# SFFV_10.net
KiCad netlist of a schematic drawn in EAGLE
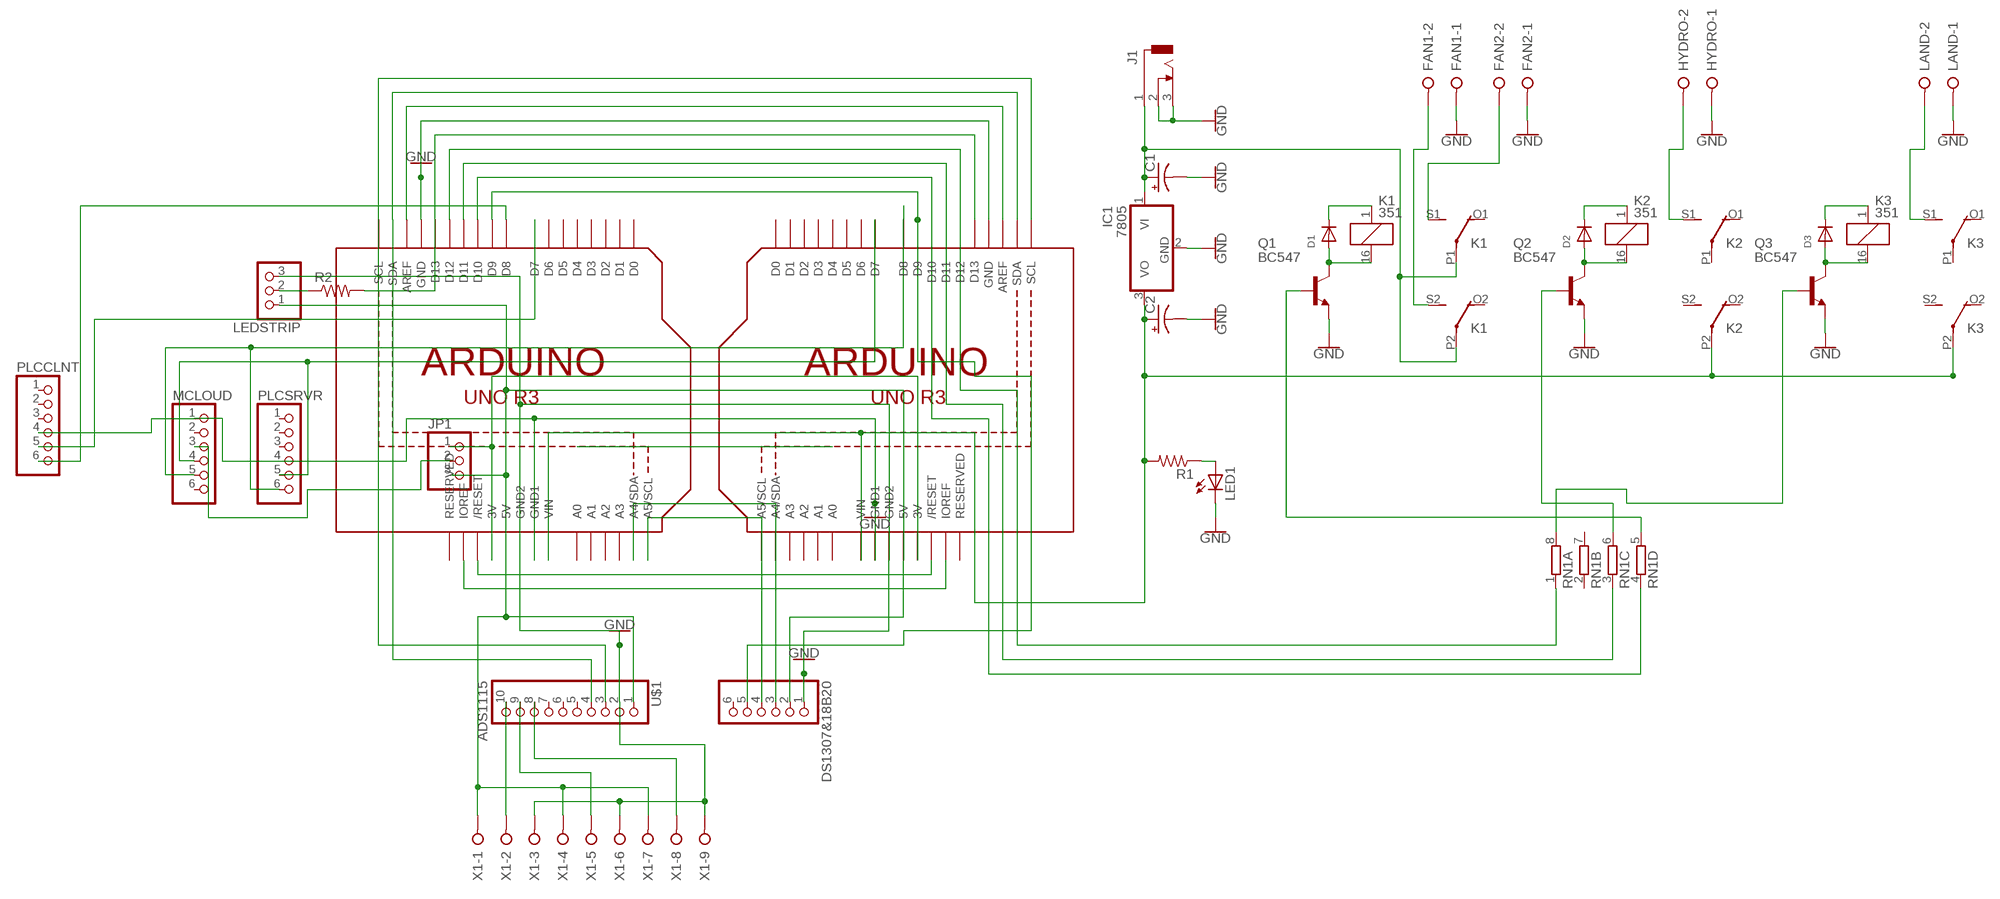
[diagram p0: schematic, sheet 1]

(export (version "E")
  (design (tool "Eeschema 10.0.6"))
  (components
    (comp (ref "C1")
      (value "CPOL-USE")
      (footprint "eagle-import:PANASONIC_E")
      (libsource (lib "eagle-import") (part "CPOL-USE"))
    )
    (comp (ref "C2")
      (value "CPOL-USE")
      (footprint "eagle-import:PANASONIC_E")
      (libsource (lib "eagle-import") (part "CPOL-USE"))
    )
    (comp (ref "D1")
      (value "DIODESMA")
      (footprint "eagle-import:SMADIODE")
      (libsource (lib "eagle-import") (part "DIODESMA"))
    )
    (comp (ref "D2")
      (value "DIODESMA")
      (footprint "eagle-import:SMADIODE")
      (libsource (lib "eagle-import") (part "DIODESMA"))
    )
    (comp (ref "D3")
      (value "DIODESMA")
      (footprint "eagle-import:SMADIODE")
      (libsource (lib "eagle-import") (part "DIODESMA"))
    )
    (comp (ref "DS1307&18B20")
      (value "PINHD-1X6B")
      (footprint "eagle-import:1X06-BIG")
      (libsource (lib "eagle-import") (part "PINHD-1X6B"))
    )
    (comp (ref "FAN1")
      (value "W237-02P")
      (footprint "eagle-import:W237-132")
      (libsource (lib "eagle-import") (part "W237-02P"))
    )
    (comp (ref "FAN2")
      (value "W237-02P")
      (footprint "eagle-import:W237-132")
      (libsource (lib "eagle-import") (part "W237-02P"))
    )
    (comp (ref "HYDRO")
      (value "W237-02P")
      (footprint "eagle-import:W237-132")
      (libsource (lib "eagle-import") (part "W237-02P"))
    )
    (comp (ref "IC1")
      (value "7805")
      (footprint "eagle-import:TO220H")
      (libsource (lib "eagle-import") (part "78T05"))
    )
    (comp (ref "J1")
      (value "DCJ0303")
      (footprint "eagle-import:DCJ0303")
      (libsource (lib "eagle-import") (part "DCJ0303"))
    )
    (comp (ref "JP1")
      (value "PINHD-1X3CB")
      (footprint "eagle-import:1X03-CLEANBIG")
      (libsource (lib "eagle-import") (part "PINHD-1X3CB"))
    )
    (comp (ref "K1")
      (value "351")
      (footprint "eagle-import:351")
      (libsource (lib "eagle-import") (part "351"))
    )
    (comp (ref "K2")
      (value "351")
      (footprint "eagle-import:351")
      (libsource (lib "eagle-import") (part "351"))
    )
    (comp (ref "K3")
      (value "351")
      (footprint "eagle-import:351")
      (libsource (lib "eagle-import") (part "351"))
    )
    (comp (ref "LAND")
      (value "W237-02P")
      (footprint "eagle-import:W237-132")
      (libsource (lib "eagle-import") (part "W237-02P"))
    )
    (comp (ref "LED1")
      (value "LED5MM")
      (footprint "eagle-import:LED5MM")
      (libsource (lib "eagle-import") (part "LED5MM"))
    )
    (comp (ref "LEDSTRIP")
      (value "PINHD-1X3")
      (footprint "eagle-import:1X03")
      (libsource (lib "eagle-import") (part "PINHD-1X3"))
    )
    (comp (ref "MCLOUD")
      (value "PINHD-1X6B")
      (footprint "eagle-import:1X06-BIG")
      (libsource (lib "eagle-import") (part "PINHD-1X6B"))
    )
    (comp (ref "PLCCLNT")
      (value "PINHD-1X6B")
      (footprint "eagle-import:1X06-BIG")
      (libsource (lib "eagle-import") (part "PINHD-1X6B"))
    )
    (comp (ref "PLCSRVR")
      (value "PINHD-1X6B")
      (footprint "eagle-import:1X06-BIG")
      (libsource (lib "eagle-import") (part "PINHD-1X6B"))
    )
    (comp (ref "Q1")
      (value "BC547")
      (footprint "eagle-import:TO92")
      (libsource (lib "eagle-import") (part "BC547"))
    )
    (comp (ref "Q2")
      (value "BC547")
      (footprint "eagle-import:TO92")
      (libsource (lib "eagle-import") (part "BC547"))
    )
    (comp (ref "Q3")
      (value "BC547")
      (footprint "eagle-import:TO92")
      (libsource (lib "eagle-import") (part "BC547"))
    )
    (comp (ref "R1")
      (value "R-US_MELF0207W")
      (footprint "eagle-import:MINI_MELF-0207W")
      (libsource (lib "eagle-import") (part "R-US_MELF0207W"))
    )
    (comp (ref "R2")
      (value "R-US_MELF0207W")
      (footprint "eagle-import:MINI_MELF-0207W")
      (libsource (lib "eagle-import") (part "R-US_MELF0207W"))
    )
    (comp (ref "RN1")
      (value "4R-NEXB38V")
      (footprint "eagle-import:EXB38V")
      (libsource (lib "eagle-import") (part "4R-NEXB38V"))
    )
    (comp (ref "U$1")
      (value "ADS1115")
      (footprint "eagle-import:1X10-BIG")
      (libsource (lib "eagle-import") (part "PINHD-1X10"))
    )
    (comp (ref "U1")
      (value "ARDUINOR3-BPLACE")
      (footprint "eagle-import:ARDUINOR3-BPLACE")
      (libsource (lib "eagle-import") (part "ARDUINOR3-BPLACE"))
    )
    (comp (ref "U2")
      (value "ARDUINOR3-BPLACE")
      (footprint "eagle-import:ARDUINOR3-BPLACE")
      (libsource (lib "eagle-import") (part "ARDUINOR3-BPLACE"))
    )
    (comp (ref "X1")
      (value "W237-09P")
      (footprint "eagle-import:W237-9P")
      (libsource (lib "eagle-import") (part "W237-09P"))
    )
  )
  (nets
    (net (code "1") (name "GND") (class "Default")
      (node (ref "C1") (pin "-") (pinfunction "-_-") (pintype "passive"))
      (node (ref "C2") (pin "-") (pinfunction "-_-") (pintype "passive"))
      (node (ref "DS1307&18B20") (pin "1") (pinfunction "1_1") (pintype "passive"))
      (node (ref "FAN1") (pin "1") (pinfunction "KL_1") (pintype "passive"))
      (node (ref "FAN2") (pin "1") (pinfunction "KL_1") (pintype "passive"))
      (node (ref "HYDRO") (pin "1") (pinfunction "KL_1") (pintype "passive"))
      (node (ref "IC1") (pin "2") (pinfunction "GND_2") (pintype "passive"))
      (node (ref "J1") (pin "2") (pinfunction "2_2") (pintype "passive"))
      (node (ref "J1") (pin "3") (pinfunction "3_3") (pintype "passive"))
      (node (ref "LAND") (pin "1") (pinfunction "KL_1") (pintype "passive"))
      (node (ref "LED1") (pin "K") (pinfunction "C_K") (pintype "passive"))
      (node (ref "LEDSTRIP") (pin "3") (pinfunction "3_3") (pintype "passive"))
      (node (ref "MCLOUD") (pin "1") (pinfunction "1_1") (pintype "passive"))
      (node (ref "PLCCLNT") (pin "4") (pinfunction "4_4") (pintype "passive"))
      (node (ref "PLCSRVR") (pin "4") (pinfunction "4_4") (pintype "passive"))
      (node (ref "Q1") (pin "1") (pinfunction "E_1") (pintype "passive"))
      (node (ref "Q2") (pin "1") (pinfunction "E_1") (pintype "passive"))
      (node (ref "Q3") (pin "1") (pinfunction "E_1") (pintype "passive"))
      (node (ref "U$1") (pin "2") (pinfunction "2_2") (pintype "passive"))
      (node (ref "U1") (pin "GND") (pinfunction "GND_GND") (pintype "power_in"))
      (node (ref "U1") (pin "GND1") (pinfunction "GND1_GND1") (pintype "power_in"))
      (node (ref "U1") (pin "GND2") (pinfunction "GND2_GND2") (pintype "power_in"))
      (node (ref "U2") (pin "GND") (pinfunction "GND_GND") (pintype "power_in"))
      (node (ref "U2") (pin "GND1") (pinfunction "GND1_GND1") (pintype "power_in"))
      (node (ref "U2") (pin "GND2") (pinfunction "GND2_GND2") (pintype "power_in"))
      (node (ref "X1") (pin "3") (pinfunction "KL_3") (pintype "passive"))
      (node (ref "X1") (pin "6") (pinfunction "KL_6") (pintype "passive"))
      (node (ref "X1") (pin "9") (pinfunction "KL_9") (pintype "passive"))
    )
    (net (code "2") (name "Net-(D1-PadC)") (class "Default")
      (node (ref "D1") (pin "C") (pinfunction "C_C") (pintype "passive"))
      (node (ref "K1") (pin "1") (pinfunction "1_1") (pintype "passive"))
    )
    (net (code "3") (name "Net-(D2-PadC)") (class "Default")
      (node (ref "D2") (pin "C") (pinfunction "C_C") (pintype "passive"))
      (node (ref "K2") (pin "1") (pinfunction "1_1") (pintype "passive"))
    )
    (net (code "4") (name "Net-(D3-PadC)") (class "Default")
      (node (ref "D3") (pin "C") (pinfunction "C_C") (pintype "passive"))
      (node (ref "K3") (pin "1") (pinfunction "1_1") (pintype "passive"))
    )
    (net (code "5") (name "Net-(DS1307&18B20-Pad5)") (class "Default")
      (node (ref "DS1307&18B20") (pin "5") (pinfunction "5_5") (pintype "passive"))
      (node (ref "U1") (pin "D9") (pinfunction "D9_D9") (pintype "bidirectional"))
      (node (ref "U2") (pin "D9") (pinfunction "D9_D9") (pintype "bidirectional"))
    )
    (net (code "6") (name "Net-(FAN1B-KL)") (class "Default")
      (node (ref "FAN1") (pin "2") (pinfunction "KL_2") (pintype "passive"))
      (node (ref "K1") (pin "S2") (pinfunction "S_S2") (pintype "passive"))
    )
    (net (code "7") (name "Net-(FAN2B-KL)") (class "Default")
      (node (ref "FAN2") (pin "2") (pinfunction "KL_2") (pintype "passive"))
      (node (ref "K1") (pin "S1") (pinfunction "S_S1") (pintype "passive"))
    )
    (net (code "8") (name "Net-(HYDROB-KL)") (class "Default")
      (node (ref "HYDRO") (pin "2") (pinfunction "KL_2") (pintype "passive"))
      (node (ref "K2") (pin "S1") (pinfunction "S_S1") (pintype "passive"))
    )
    (net (code "9") (name "Net-(IC1-VI)") (class "Default")
      (node (ref "C1") (pin "+") (pinfunction "+_+") (pintype "passive"))
      (node (ref "IC1") (pin "1") (pinfunction "VI_1") (pintype "input"))
      (node (ref "J1") (pin "1") (pinfunction "1_1") (pintype "passive"))
      (node (ref "K1") (pin "P1") (pinfunction "P_P1") (pintype "passive"))
      (node (ref "K1") (pin "P2") (pinfunction "P_P2") (pintype "passive"))
    )
    (net (code "10") (name "Net-(IC1-VO)") (class "Default")
      (node (ref "C2") (pin "+") (pinfunction "+_+") (pintype "passive"))
      (node (ref "IC1") (pin "3") (pinfunction "VO_3") (pintype "passive"))
      (node (ref "K2") (pin "P2") (pinfunction "P_P2") (pintype "passive"))
      (node (ref "K3") (pin "P2") (pinfunction "P_P2") (pintype "passive"))
      (node (ref "R1") (pin "2") (pinfunction "2_2") (pintype "passive"))
      (node (ref "U1") (pin "VIN") (pinfunction "VIN_VIN") (pintype "power_in"))
      (node (ref "U2") (pin "VIN") (pinfunction "VIN_VIN") (pintype "power_in"))
    )
    (net (code "11") (name "Net-(JP1-Pad1)") (class "Default")
      (node (ref "JP1") (pin "1") (pinfunction "1_1") (pintype "passive"))
      (node (ref "U1") (pin "3V") (pinfunction "3V_3V") (pintype "power_in"))
      (node (ref "U2") (pin "3V") (pinfunction "3V_3V") (pintype "power_in"))
    )
    (net (code "12") (name "Net-(JP1-Pad2)") (class "Default")
      (node (ref "JP1") (pin "2") (pinfunction "2_2") (pintype "passive"))
      (node (ref "MCLOUD") (pin "3") (pinfunction "3_3") (pintype "passive"))
    )
    (net (code "13") (name "Net-(K1A-2)") (class "Default")
      (node (ref "D1") (pin "A") (pinfunction "A_A") (pintype "passive"))
      (node (ref "K1") (pin "16") (pinfunction "2_16") (pintype "passive"))
      (node (ref "Q1") (pin "3") (pinfunction "C_3") (pintype "passive"))
    )
    (net (code "14") (name "Net-(K2A-2)") (class "Default")
      (node (ref "D2") (pin "A") (pinfunction "A_A") (pintype "passive"))
      (node (ref "K2") (pin "16") (pinfunction "2_16") (pintype "passive"))
      (node (ref "Q2") (pin "3") (pinfunction "C_3") (pintype "passive"))
    )
    (net (code "15") (name "Net-(K3A-2)") (class "Default")
      (node (ref "D3") (pin "A") (pinfunction "A_A") (pintype "passive"))
      (node (ref "K3") (pin "16") (pinfunction "2_16") (pintype "passive"))
      (node (ref "Q3") (pin "3") (pinfunction "C_3") (pintype "passive"))
    )
    (net (code "16") (name "Net-(K3B-S)") (class "Default")
      (node (ref "K3") (pin "S1") (pinfunction "S_S1") (pintype "passive"))
      (node (ref "LAND") (pin "2") (pinfunction "KL_2") (pintype "passive"))
    )
    (net (code "17") (name "Net-(LED1-PadA)") (class "Default")
      (node (ref "LED1") (pin "A") (pinfunction "A_A") (pintype "passive"))
      (node (ref "R1") (pin "1") (pinfunction "1_1") (pintype "passive"))
    )
    (net (code "18") (name "Net-(LEDSTRIP-Pad2)") (class "Default")
      (node (ref "LEDSTRIP") (pin "2") (pinfunction "2_2") (pintype "passive"))
      (node (ref "R2") (pin "1") (pinfunction "1_1") (pintype "passive"))
    )
    (net (code "19") (name "Net-(MCLOUD-Pad4)") (class "Default")
      (node (ref "MCLOUD") (pin "4") (pinfunction "4_4") (pintype "passive"))
      (node (ref "PLCSRVR") (pin "5") (pinfunction "5_5") (pintype "passive"))
      (node (ref "U2") (pin "D7") (pinfunction "D7_D7") (pintype "bidirectional"))
    )
    (net (code "20") (name "Net-(MCLOUD-Pad5)") (class "Default")
      (node (ref "MCLOUD") (pin "5") (pinfunction "5_5") (pintype "passive"))
      (node (ref "PLCSRVR") (pin "6") (pinfunction "6_6") (pintype "passive"))
      (node (ref "U2") (pin "D8") (pinfunction "D8_D8") (pintype "bidirectional"))
    )
    (net (code "21") (name "Net-(PLCCLNT-Pad5)") (class "Default")
      (node (ref "PLCCLNT") (pin "5") (pinfunction "5_5") (pintype "passive"))
      (node (ref "U1") (pin "D7") (pinfunction "D7_D7") (pintype "bidirectional"))
    )
    (net (code "22") (name "Net-(PLCCLNT-Pad6)") (class "Default")
      (node (ref "PLCCLNT") (pin "6") (pinfunction "6_6") (pintype "passive"))
      (node (ref "U1") (pin "D8") (pinfunction "D8_D8") (pintype "bidirectional"))
    )
    (net (code "23") (name "Net-(Q1-B)") (class "Default")
      (node (ref "Q1") (pin "2") (pinfunction "B_2") (pintype "passive"))
      (node (ref "RN1") (pin "5") (pinfunction "2_5") (pintype "passive"))
    )
    (net (code "24") (name "Net-(Q2-B)") (class "Default")
      (node (ref "Q2") (pin "2") (pinfunction "B_2") (pintype "passive"))
      (node (ref "RN1") (pin "6") (pinfunction "2_6") (pintype "passive"))
    )
    (net (code "25") (name "Net-(Q3-B)") (class "Default")
      (node (ref "Q3") (pin "2") (pinfunction "B_2") (pintype "passive"))
      (node (ref "RN1") (pin "8") (pinfunction "2_8") (pintype "passive"))
    )
    (net (code "26") (name "Net-(R2-Pad2)") (class "Default")
      (node (ref "R2") (pin "2") (pinfunction "2_2") (pintype "passive"))
      (node (ref "U1") (pin "D13") (pinfunction "D13_D13") (pintype "bidirectional"))
      (node (ref "U2") (pin "D13") (pinfunction "D13_D13") (pintype "bidirectional"))
    )
    (net (code "27") (name "Net-(RN1-Pad1)") (class "Default")
      (node (ref "RN1") (pin "1") (pinfunction "1_1") (pintype "passive"))
      (node (ref "U1") (pin "D12") (pinfunction "D12_D12") (pintype "bidirectional"))
      (node (ref "U2") (pin "D12") (pinfunction "D12_D12") (pintype "bidirectional"))
    )
    (net (code "28") (name "Net-(RN1C-1)") (class "Default")
      (node (ref "RN1") (pin "3") (pinfunction "1_3") (pintype "passive"))
      (node (ref "U1") (pin "D11") (pinfunction "D11_D11") (pintype "bidirectional"))
      (node (ref "U2") (pin "D11") (pinfunction "D11_D11") (pintype "bidirectional"))
    )
    (net (code "29") (name "Net-(RN1D-1)") (class "Default")
      (node (ref "RN1") (pin "4") (pinfunction "1_4") (pintype "passive"))
      (node (ref "U1") (pin "D10") (pinfunction "D10_D10") (pintype "bidirectional"))
      (node (ref "U2") (pin "D10") (pinfunction "D10_D10") (pintype "bidirectional"))
    )
    (net (code "30") (name "Net-(U$1-Pad3)") (class "Default")
      (node (ref "U$1") (pin "3") (pinfunction "3_3") (pintype "passive"))
      (node (ref "U1") (pin "SCL") (pinfunction "SCL_SCL") (pintype "bidirectional"))
      (node (ref "U2") (pin "SCL") (pinfunction "SCL_SCL") (pintype "bidirectional"))
    )
    (net (code "31") (name "Net-(U$1-Pad4)") (class "Default")
      (node (ref "U$1") (pin "4") (pinfunction "4_4") (pintype "passive"))
      (node (ref "U1") (pin "SDA") (pinfunction "SDA_SDA") (pintype "bidirectional"))
      (node (ref "U2") (pin "SDA") (pinfunction "SDA_SDA") (pintype "bidirectional"))
    )
    (net (code "32") (name "Net-(U1-A4{slash}SDA)") (class "Default")
      (node (ref "DS1307&18B20") (pin "3") (pinfunction "3_3") (pintype "passive"))
      (node (ref "U1") (pin "A4") (pinfunction "A4/SDA_A4") (pintype "bidirectional"))
      (node (ref "U2") (pin "A4") (pinfunction "A4/SDA_A4") (pintype "bidirectional"))
    )
    (net (code "33") (name "Net-(U1-A5{slash}SCL)") (class "Default")
      (node (ref "DS1307&18B20") (pin "4") (pinfunction "4_4") (pintype "passive"))
      (node (ref "U1") (pin "A5") (pinfunction "A5/SCL_A5") (pintype "bidirectional"))
      (node (ref "U2") (pin "A5") (pinfunction "A5/SCL_A5") (pintype "bidirectional"))
    )
    (net (code "34") (name "Net-(U1-PadAREF)") (class "Default")
      (node (ref "U1") (pin "AREF") (pinfunction "AREF_AREF") (pintype "bidirectional"))
      (node (ref "U2") (pin "AREF") (pinfunction "AREF_AREF") (pintype "bidirectional"))
    )
    (net (code "35") (name "Net-(U1-PadIOREF)") (class "Default")
      (node (ref "U1") (pin "IOREF") (pinfunction "IOREF_IOREF") (pintype "output"))
      (node (ref "U2") (pin "IOREF") (pinfunction "IOREF_IOREF") (pintype "output"))
    )
    (net (code "36") (name "Net-(U1-{slash}RESET)") (class "Default")
      (node (ref "U1") (pin "RESET") (pinfunction "/RESET_RESET") (pintype "bidirectional"))
      (node (ref "U2") (pin "RESET") (pinfunction "/RESET_RESET") (pintype "bidirectional"))
    )
    (net (code "37") (name "Net-(X1A-KL)") (class "Default")
      (node (ref "DS1307&18B20") (pin "2") (pinfunction "2_2") (pintype "passive"))
      (node (ref "JP1") (pin "3") (pinfunction "3_3") (pintype "passive"))
      (node (ref "LEDSTRIP") (pin "1") (pinfunction "1_1") (pintype "passive"))
      (node (ref "U$1") (pin "1") (pinfunction "1_1") (pintype "passive"))
      (node (ref "U1") (pin "5V") (pinfunction "5V_5V") (pintype "power_in"))
      (node (ref "U2") (pin "5V") (pinfunction "5V_5V") (pintype "power_in"))
      (node (ref "X1") (pin "1") (pinfunction "KL_1") (pintype "passive"))
      (node (ref "X1") (pin "4") (pinfunction "KL_4") (pintype "passive"))
      (node (ref "X1") (pin "7") (pinfunction "KL_7") (pintype "passive"))
    )
    (net (code "38") (name "Net-(X1B-KL)") (class "Default")
      (node (ref "U$1") (pin "10") (pinfunction "10_10") (pintype "passive"))
      (node (ref "X1") (pin "2") (pinfunction "KL_2") (pintype "passive"))
    )
    (net (code "39") (name "Net-(X1E-KL)") (class "Default")
      (node (ref "U$1") (pin "9") (pinfunction "9_9") (pintype "passive"))
      (node (ref "X1") (pin "5") (pinfunction "KL_5") (pintype "passive"))
    )
    (net (code "40") (name "Net-(X1H-KL)") (class "Default")
      (node (ref "U$1") (pin "8") (pinfunction "8_8") (pintype "passive"))
      (node (ref "X1") (pin "8") (pinfunction "KL_8") (pintype "passive"))
    )
    (net (code "41") (name "unconnected-(DS1307&18B20-Pad6)") (class "Default")
      (node (ref "DS1307&18B20") (pin "6") (pinfunction "6_6") (pintype "passive"))
    )
    (net (code "42") (name "unconnected-(K1B-O-PadO1)") (class "Default")
      (node (ref "K1") (pin "O1") (pinfunction "O_O1") (pintype "passive"))
    )
    (net (code "43") (name "unconnected-(K1C-O-PadO2)") (class "Default")
      (node (ref "K1") (pin "O2") (pinfunction "O_O2") (pintype "passive"))
    )
    (net (code "44") (name "unconnected-(K2B-O-PadO1)") (class "Default")
      (node (ref "K2") (pin "O1") (pinfunction "O_O1") (pintype "passive"))
    )
    (net (code "45") (name "unconnected-(K2B-P-PadP1)") (class "Default")
      (node (ref "K2") (pin "P1") (pinfunction "P_P1") (pintype "passive"))
    )
    (net (code "46") (name "unconnected-(K2C-O-PadO2)") (class "Default")
      (node (ref "K2") (pin "O2") (pinfunction "O_O2") (pintype "passive"))
    )
    (net (code "47") (name "unconnected-(K2C-S-PadS2)") (class "Default")
      (node (ref "K2") (pin "S2") (pinfunction "S_S2") (pintype "passive"))
    )
    (net (code "48") (name "unconnected-(K3B-O-PadO1)") (class "Default")
      (node (ref "K3") (pin "O1") (pinfunction "O_O1") (pintype "passive"))
    )
    (net (code "49") (name "unconnected-(K3B-P-PadP1)") (class "Default")
      (node (ref "K3") (pin "P1") (pinfunction "P_P1") (pintype "passive"))
    )
    (net (code "50") (name "unconnected-(K3C-O-PadO2)") (class "Default")
      (node (ref "K3") (pin "O2") (pinfunction "O_O2") (pintype "passive"))
    )
    (net (code "51") (name "unconnected-(K3C-S-PadS2)") (class "Default")
      (node (ref "K3") (pin "S2") (pinfunction "S_S2") (pintype "passive"))
    )
    (net (code "52") (name "unconnected-(MCLOUD-Pad2)") (class "Default")
      (node (ref "MCLOUD") (pin "2") (pinfunction "2_2") (pintype "passive"))
    )
    (net (code "53") (name "unconnected-(MCLOUD-Pad6)") (class "Default")
      (node (ref "MCLOUD") (pin "6") (pinfunction "6_6") (pintype "passive"))
    )
    (net (code "54") (name "unconnected-(PLCCLNT-Pad1)") (class "Default")
      (node (ref "PLCCLNT") (pin "1") (pinfunction "1_1") (pintype "passive"))
    )
    (net (code "55") (name "unconnected-(PLCCLNT-Pad2)") (class "Default")
      (node (ref "PLCCLNT") (pin "2") (pinfunction "2_2") (pintype "passive"))
    )
    (net (code "56") (name "unconnected-(PLCCLNT-Pad3)") (class "Default")
      (node (ref "PLCCLNT") (pin "3") (pinfunction "3_3") (pintype "passive"))
    )
    (net (code "57") (name "unconnected-(PLCSRVR-Pad1)") (class "Default")
      (node (ref "PLCSRVR") (pin "1") (pinfunction "1_1") (pintype "passive"))
    )
    (net (code "58") (name "unconnected-(PLCSRVR-Pad2)") (class "Default")
      (node (ref "PLCSRVR") (pin "2") (pinfunction "2_2") (pintype "passive"))
    )
    (net (code "59") (name "unconnected-(PLCSRVR-Pad3)") (class "Default")
      (node (ref "PLCSRVR") (pin "3") (pinfunction "3_3") (pintype "passive"))
    )
    (net (code "60") (name "unconnected-(RN1B-1-Pad2)") (class "Default")
      (node (ref "RN1") (pin "2") (pinfunction "1_2") (pintype "passive"))
    )
    (net (code "61") (name "unconnected-(RN1B-2-Pad7)") (class "Default")
      (node (ref "RN1") (pin "7") (pinfunction "2_7") (pintype "passive"))
    )
    (net (code "62") (name "unconnected-(U$1-Pad5)") (class "Default")
      (node (ref "U$1") (pin "5") (pinfunction "5_5") (pintype "passive"))
    )
    (net (code "63") (name "unconnected-(U$1-Pad6)") (class "Default")
      (node (ref "U$1") (pin "6") (pinfunction "6_6") (pintype "passive"))
    )
    (net (code "64") (name "unconnected-(U$1-Pad7)") (class "Default")
      (node (ref "U$1") (pin "7") (pinfunction "7_7") (pintype "passive"))
    )
    (net (code "65") (name "unconnected-(U1-PadA0)") (class "Default")
      (node (ref "U1") (pin "A0") (pinfunction "A0_A0") (pintype "bidirectional"))
    )
    (net (code "66") (name "unconnected-(U1-PadA1)") (class "Default")
      (node (ref "U1") (pin "A1") (pinfunction "A1_A1") (pintype "bidirectional"))
    )
    (net (code "67") (name "unconnected-(U1-PadA2)") (class "Default")
      (node (ref "U1") (pin "A2") (pinfunction "A2_A2") (pintype "bidirectional"))
    )
    (net (code "68") (name "unconnected-(U1-PadA3)") (class "Default")
      (node (ref "U1") (pin "A3") (pinfunction "A3_A3") (pintype "bidirectional"))
    )
    (net (code "69") (name "unconnected-(U1-PadD0)") (class "Default")
      (node (ref "U1") (pin "D0") (pinfunction "D0_D0") (pintype "bidirectional"))
    )
    (net (code "70") (name "unconnected-(U1-PadD1)") (class "Default")
      (node (ref "U1") (pin "D1") (pinfunction "D1_D1") (pintype "bidirectional"))
    )
    (net (code "71") (name "unconnected-(U1-PadD2)") (class "Default")
      (node (ref "U1") (pin "D2") (pinfunction "D2_D2") (pintype "bidirectional"))
    )
    (net (code "72") (name "unconnected-(U1-PadD3)") (class "Default")
      (node (ref "U1") (pin "D3") (pinfunction "D3_D3") (pintype "bidirectional"))
    )
    (net (code "73") (name "unconnected-(U1-PadD4)") (class "Default")
      (node (ref "U1") (pin "D4") (pinfunction "D4_D4") (pintype "bidirectional"))
    )
    (net (code "74") (name "unconnected-(U1-PadD5)") (class "Default")
      (node (ref "U1") (pin "D5") (pinfunction "D5_D5") (pintype "bidirectional"))
    )
    (net (code "75") (name "unconnected-(U1-PadD6)") (class "Default")
      (node (ref "U1") (pin "D6") (pinfunction "D6_D6") (pintype "bidirectional"))
    )
    (net (code "76") (name "unconnected-(U1-PadRESERVED)") (class "Default")
      (node (ref "U1") (pin "RESERVED") (pinfunction "RESERVED_RESERVED") (pintype "no_connect"))
    )
    (net (code "77") (name "unconnected-(U2-PadA0)") (class "Default")
      (node (ref "U2") (pin "A0") (pinfunction "A0_A0") (pintype "bidirectional"))
    )
    (net (code "78") (name "unconnected-(U2-PadA1)") (class "Default")
      (node (ref "U2") (pin "A1") (pinfunction "A1_A1") (pintype "bidirectional"))
    )
    (net (code "79") (name "unconnected-(U2-PadA2)") (class "Default")
      (node (ref "U2") (pin "A2") (pinfunction "A2_A2") (pintype "bidirectional"))
    )
    (net (code "80") (name "unconnected-(U2-PadA3)") (class "Default")
      (node (ref "U2") (pin "A3") (pinfunction "A3_A3") (pintype "bidirectional"))
    )
    (net (code "81") (name "unconnected-(U2-PadD0)") (class "Default")
      (node (ref "U2") (pin "D0") (pinfunction "D0_D0") (pintype "bidirectional"))
    )
    (net (code "82") (name "unconnected-(U2-PadD1)") (class "Default")
      (node (ref "U2") (pin "D1") (pinfunction "D1_D1") (pintype "bidirectional"))
    )
    (net (code "83") (name "unconnected-(U2-PadD2)") (class "Default")
      (node (ref "U2") (pin "D2") (pinfunction "D2_D2") (pintype "bidirectional"))
    )
    (net (code "84") (name "unconnected-(U2-PadD3)") (class "Default")
      (node (ref "U2") (pin "D3") (pinfunction "D3_D3") (pintype "bidirectional"))
    )
    (net (code "85") (name "unconnected-(U2-PadD4)") (class "Default")
      (node (ref "U2") (pin "D4") (pinfunction "D4_D4") (pintype "bidirectional"))
    )
    (net (code "86") (name "unconnected-(U2-PadD5)") (class "Default")
      (node (ref "U2") (pin "D5") (pinfunction "D5_D5") (pintype "bidirectional"))
    )
    (net (code "87") (name "unconnected-(U2-PadD6)") (class "Default")
      (node (ref "U2") (pin "D6") (pinfunction "D6_D6") (pintype "bidirectional"))
    )
    (net (code "88") (name "unconnected-(U2-PadRESERVED)") (class "Default")
      (node (ref "U2") (pin "RESERVED") (pinfunction "RESERVED_RESERVED") (pintype "no_connect"))
    )
  )
)
